# I2C-7-Segment-Backpack-dot56inch.net
KiCad netlist of a schematic drawn in EAGLE
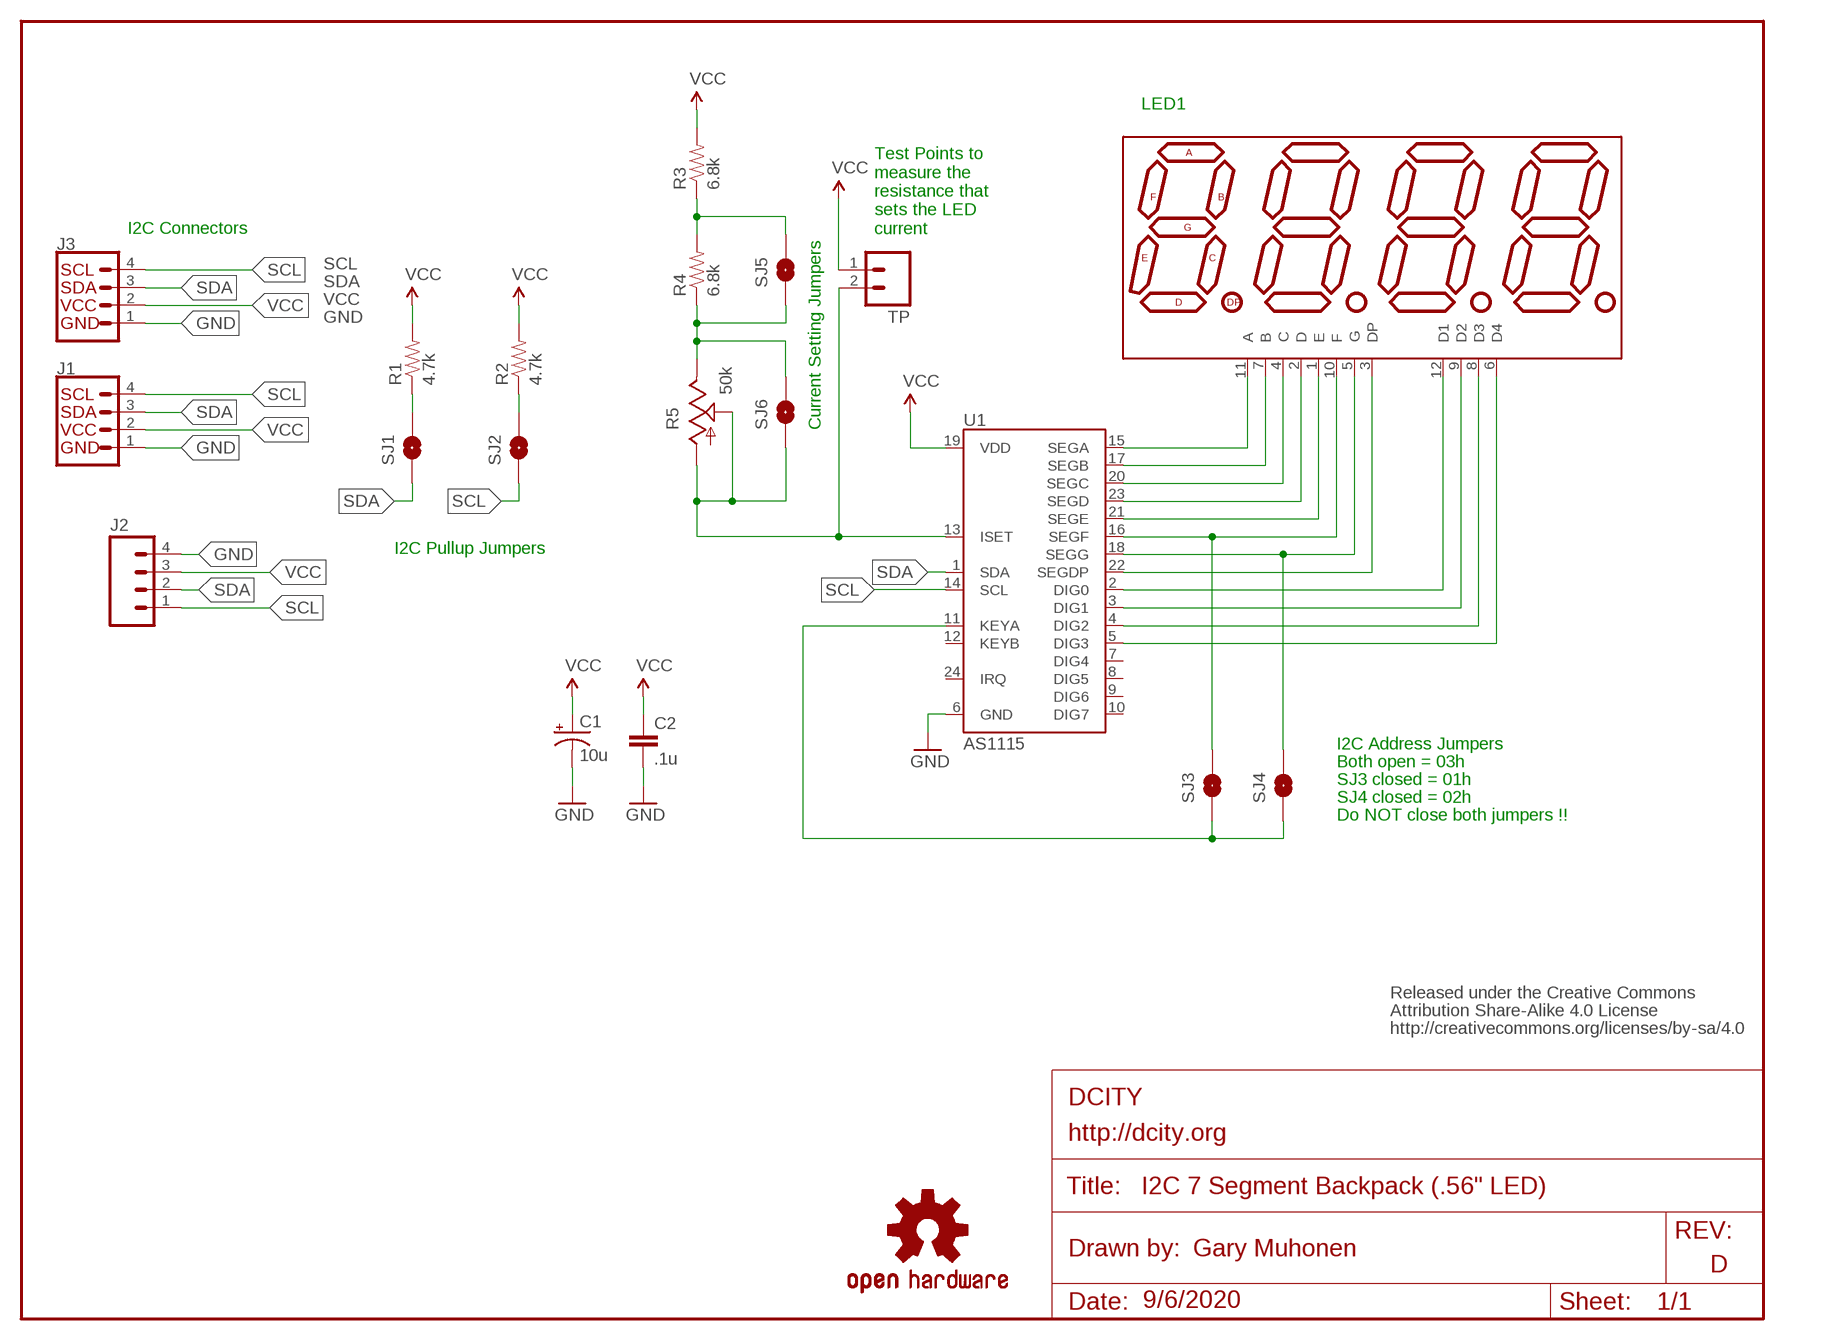
[diagram p0: schematic, sheet 1]

(export (version "E")
  (design (tool "Eeschema 10.0.6"))
  (components
    (comp (ref "C1")
      (value "10u")
      (footprint "eagle-import:0805-POL")
      (libsource (lib "eagle-import") (part "CAP_POL0805"))
    )
    (comp (ref "C2")
      (value ".1u")
      (footprint "eagle-import:0805-CAP")
      (libsource (lib "eagle-import") (part "CAP0805"))
    )
    (comp (ref "DISP1")
      (value "LED1")
      (footprint "eagle-import:7-SEGMENT-4DIGIT-PT6")
      (libsource (lib "eagle-import") (part "7-SEGMENT-4DIGIT-COUNTER-PT6"))
    )
    (comp (ref "J1")
      (value "QWIIC_RIGHT_ANGLE")
      (footprint "eagle-import:JST04_1MM_RA")
      (libsource (lib "eagle-import") (part "QWIIC_CONNECTORJS-1MM"))
    )
    (comp (ref "J2")
      (value "M04LOCK")
      (footprint "eagle-import:1X04_LOCK")
      (libsource (lib "eagle-import") (part "M04LOCK"))
    )
    (comp (ref "J3")
      (value "QWIIC_RIGHT_ANGLE")
      (footprint "eagle-import:JST04_1MM_RA")
      (libsource (lib "eagle-import") (part "QWIIC_CONNECTORJS-1MM"))
    )
    (comp (ref "LOGO1")
      (value "OSHW-LOGOS")
      (footprint "eagle-import:OSHW-LOGO-S")
      (libsource (lib "eagle-import") (part "OSHW-LOGOS"))
    )
    (comp (ref "R1")
      (value "4.7k")
      (footprint "eagle-import:0805-RES")
      (libsource (lib "eagle-import") (part "RESISTOR0805"))
    )
    (comp (ref "R2")
      (value "4.7k")
      (footprint "eagle-import:0805-RES")
      (libsource (lib "eagle-import") (part "RESISTOR0805"))
    )
    (comp (ref "R3")
      (value "6.8k")
      (footprint "eagle-import:0805-RES")
      (libsource (lib "eagle-import") (part "RESISTOR0805"))
    )
    (comp (ref "R4")
      (value "6.8k")
      (footprint "eagle-import:0805-RES")
      (libsource (lib "eagle-import") (part "RESISTOR0805"))
    )
    (comp (ref "R5")
      (value "50k")
      (footprint "eagle-import:POT-TC33X")
      (libsource (lib "eagle-import") (part "POT-TC33X"))
    )
    (comp (ref "SJ1")
      (value "SOLDERJUMPERNO")
      (footprint "eagle-import:SJ_2S-NO")
      (libsource (lib "eagle-import") (part "SOLDERJUMPERNO"))
    )
    (comp (ref "SJ2")
      (value "SOLDERJUMPERNO")
      (footprint "eagle-import:SJ_2S-NO")
      (libsource (lib "eagle-import") (part "SOLDERJUMPERNO"))
    )
    (comp (ref "SJ3")
      (value "SOLDERJUMPERNO")
      (footprint "eagle-import:SJ_2S-NO")
      (libsource (lib "eagle-import") (part "SOLDERJUMPERNO"))
    )
    (comp (ref "SJ4")
      (value "SOLDERJUMPERNO")
      (footprint "eagle-import:SJ_2S-NO")
      (libsource (lib "eagle-import") (part "SOLDERJUMPERNO"))
    )
    (comp (ref "SJ5")
      (value "SOLDERJUMPERNO")
      (footprint "eagle-import:SJ_2S-NO")
      (libsource (lib "eagle-import") (part "SOLDERJUMPERNO"))
    )
    (comp (ref "SJ6")
      (value "SOLDERJUMPERNO")
      (footprint "eagle-import:SJ_2S-NO")
      (libsource (lib "eagle-import") (part "SOLDERJUMPERNO"))
    )
    (comp (ref "TP")
      (value "M02PTH")
      (footprint "eagle-import:1X02")
      (libsource (lib "eagle-import") (part "M02PTH"))
    )
    (comp (ref "U$2")
      (value "CREATIVE_COMMONS")
      (footprint "eagle-import:CREATIVE_COMMONS")
      (libsource (lib "eagle-import") (part "CREATIVE_COMMONS"))
    )
    (comp (ref "U1")
      (value "AS1115")
      (footprint "eagle-import:TSSOP-24")
      (libsource (lib "eagle-import") (part "AS1115-LP"))
    )
  )
  (nets
    (net (code "1") (name "GND") (class "Default")
      (node (ref "C1") (pin "-") (pinfunction "-_-") (pintype "passive"))
      (node (ref "C2") (pin "2") (pinfunction "2_2") (pintype "passive"))
      (node (ref "J1") (pin "1") (pinfunction "1_1") (pintype "power_in"))
      (node (ref "J2") (pin "4") (pinfunction "4_4") (pintype "passive"))
      (node (ref "J3") (pin "1") (pinfunction "1_1") (pintype "power_in"))
      (node (ref "U1") (pin "6") (pinfunction "GND_6") (pintype "bidirectional"))
    )
    (net (code "2") (name "Net-(DISP1-A)") (class "Default")
      (node (ref "DISP1") (pin "11") (pinfunction "A_11") (pintype "bidirectional"))
      (node (ref "U1") (pin "15") (pinfunction "SEGA_15") (pintype "bidirectional"))
    )
    (net (code "3") (name "Net-(DISP1-B)") (class "Default")
      (node (ref "DISP1") (pin "7") (pinfunction "B_7") (pintype "bidirectional"))
      (node (ref "U1") (pin "17") (pinfunction "SEGB_17") (pintype "bidirectional"))
    )
    (net (code "4") (name "Net-(DISP1-C)") (class "Default")
      (node (ref "DISP1") (pin "4") (pinfunction "C_4") (pintype "bidirectional"))
      (node (ref "U1") (pin "20") (pinfunction "SEGC_20") (pintype "bidirectional"))
    )
    (net (code "5") (name "Net-(DISP1-D)") (class "Default")
      (node (ref "DISP1") (pin "2") (pinfunction "D_2") (pintype "bidirectional"))
      (node (ref "U1") (pin "23") (pinfunction "SEGD_23") (pintype "bidirectional"))
    )
    (net (code "6") (name "Net-(DISP1-D1)") (class "Default")
      (node (ref "DISP1") (pin "12") (pinfunction "D1_12") (pintype "bidirectional"))
      (node (ref "U1") (pin "2") (pinfunction "DIG0_2") (pintype "bidirectional"))
    )
    (net (code "7") (name "Net-(DISP1-D2)") (class "Default")
      (node (ref "DISP1") (pin "9") (pinfunction "D2_9") (pintype "bidirectional"))
      (node (ref "U1") (pin "3") (pinfunction "DIG1_3") (pintype "bidirectional"))
    )
    (net (code "8") (name "Net-(DISP1-D3)") (class "Default")
      (node (ref "DISP1") (pin "8") (pinfunction "D3_8") (pintype "bidirectional"))
      (node (ref "U1") (pin "4") (pinfunction "DIG2_4") (pintype "bidirectional"))
    )
    (net (code "9") (name "Net-(DISP1-D4)") (class "Default")
      (node (ref "DISP1") (pin "6") (pinfunction "D4_6") (pintype "bidirectional"))
      (node (ref "U1") (pin "5") (pinfunction "DIG3_5") (pintype "bidirectional"))
    )
    (net (code "10") (name "Net-(DISP1-DP)") (class "Default")
      (node (ref "DISP1") (pin "3") (pinfunction "DP_3") (pintype "bidirectional"))
      (node (ref "U1") (pin "22") (pinfunction "SEGDP_22") (pintype "bidirectional"))
    )
    (net (code "11") (name "Net-(DISP1-E)") (class "Default")
      (node (ref "DISP1") (pin "1") (pinfunction "E_1") (pintype "bidirectional"))
      (node (ref "U1") (pin "21") (pinfunction "SEGE_21") (pintype "bidirectional"))
    )
    (net (code "12") (name "Net-(DISP1-F)") (class "Default")
      (node (ref "DISP1") (pin "10") (pinfunction "F_10") (pintype "bidirectional"))
      (node (ref "SJ3") (pin "2") (pinfunction "2_2") (pintype "passive"))
      (node (ref "U1") (pin "16") (pinfunction "SEGF_16") (pintype "bidirectional"))
    )
    (net (code "13") (name "Net-(DISP1-G)") (class "Default")
      (node (ref "DISP1") (pin "5") (pinfunction "G_5") (pintype "bidirectional"))
      (node (ref "SJ4") (pin "2") (pinfunction "2_2") (pintype "passive"))
      (node (ref "U1") (pin "18") (pinfunction "SEGG_18") (pintype "bidirectional"))
    )
    (net (code "14") (name "Net-(R1-Pad1)") (class "Default")
      (node (ref "R1") (pin "1") (pinfunction "1_1") (pintype "passive"))
      (node (ref "SJ1") (pin "2") (pinfunction "2_2") (pintype "passive"))
    )
    (net (code "15") (name "Net-(R2-Pad1)") (class "Default")
      (node (ref "R2") (pin "1") (pinfunction "1_1") (pintype "passive"))
      (node (ref "SJ2") (pin "2") (pinfunction "2_2") (pintype "passive"))
    )
    (net (code "16") (name "Net-(R3-Pad1)") (class "Default")
      (node (ref "R3") (pin "1") (pinfunction "1_1") (pintype "passive"))
      (node (ref "R4") (pin "2") (pinfunction "2_2") (pintype "passive"))
      (node (ref "SJ5") (pin "2") (pinfunction "2_2") (pintype "passive"))
    )
    (net (code "17") (name "Net-(R5-A)") (class "Default")
      (node (ref "R5") (pin "1") (pinfunction "A_1") (pintype "passive"))
      (node (ref "R5") (pin "2") (pinfunction "S_2") (pintype "passive"))
      (node (ref "SJ6") (pin "1") (pinfunction "1_1") (pintype "passive"))
      (node (ref "TP") (pin "2") (pinfunction "2_2") (pintype "passive"))
      (node (ref "U1") (pin "13") (pinfunction "ISET_13") (pintype "bidirectional"))
    )
    (net (code "18") (name "Net-(R5-E)") (class "Default")
      (node (ref "R4") (pin "1") (pinfunction "1_1") (pintype "passive"))
      (node (ref "R5") (pin "3") (pinfunction "E_3") (pintype "passive"))
      (node (ref "SJ5") (pin "1") (pinfunction "1_1") (pintype "passive"))
      (node (ref "SJ6") (pin "2") (pinfunction "2_2") (pintype "passive"))
    )
    (net (code "19") (name "Net-(U1-KEYA)") (class "Default")
      (node (ref "SJ3") (pin "1") (pinfunction "1_1") (pintype "passive"))
      (node (ref "SJ4") (pin "1") (pinfunction "1_1") (pintype "passive"))
      (node (ref "U1") (pin "11") (pinfunction "KEYA_11") (pintype "bidirectional"))
    )
    (net (code "20") (name "SCL") (class "Default")
      (node (ref "J1") (pin "4") (pinfunction "4_4") (pintype "passive"))
      (node (ref "J2") (pin "1") (pinfunction "1_1") (pintype "passive"))
      (node (ref "J3") (pin "4") (pinfunction "4_4") (pintype "passive"))
      (node (ref "SJ2") (pin "1") (pinfunction "1_1") (pintype "passive"))
      (node (ref "U1") (pin "14") (pinfunction "SCL_14") (pintype "bidirectional"))
    )
    (net (code "21") (name "SDA") (class "Default")
      (node (ref "J1") (pin "3") (pinfunction "3_3") (pintype "passive"))
      (node (ref "J2") (pin "2") (pinfunction "2_2") (pintype "passive"))
      (node (ref "J3") (pin "3") (pinfunction "3_3") (pintype "passive"))
      (node (ref "SJ1") (pin "1") (pinfunction "1_1") (pintype "passive"))
      (node (ref "U1") (pin "1") (pinfunction "SDA_1") (pintype "bidirectional"))
    )
    (net (code "22") (name "VCC") (class "Default")
      (node (ref "C1") (pin "+") (pinfunction "+_+") (pintype "passive"))
      (node (ref "C2") (pin "1") (pinfunction "1_1") (pintype "passive"))
      (node (ref "J1") (pin "2") (pinfunction "2_2") (pintype "power_in"))
      (node (ref "J2") (pin "3") (pinfunction "3_3") (pintype "passive"))
      (node (ref "J3") (pin "2") (pinfunction "2_2") (pintype "power_in"))
      (node (ref "R1") (pin "2") (pinfunction "2_2") (pintype "passive"))
      (node (ref "R2") (pin "2") (pinfunction "2_2") (pintype "passive"))
      (node (ref "R3") (pin "2") (pinfunction "2_2") (pintype "passive"))
      (node (ref "TP") (pin "1") (pinfunction "1_1") (pintype "passive"))
      (node (ref "U1") (pin "19") (pinfunction "VDD_19") (pintype "bidirectional"))
    )
    (net (code "23") (name "unconnected-(U1-DIG4-Pad7)") (class "Default")
      (node (ref "U1") (pin "7") (pinfunction "DIG4_7") (pintype "bidirectional"))
    )
    (net (code "24") (name "unconnected-(U1-DIG5-Pad8)") (class "Default")
      (node (ref "U1") (pin "8") (pinfunction "DIG5_8") (pintype "bidirectional"))
    )
    (net (code "25") (name "unconnected-(U1-DIG6-Pad9)") (class "Default")
      (node (ref "U1") (pin "9") (pinfunction "DIG6_9") (pintype "bidirectional"))
    )
    (net (code "26") (name "unconnected-(U1-DIG7-Pad10)") (class "Default")
      (node (ref "U1") (pin "10") (pinfunction "DIG7_10") (pintype "bidirectional"))
    )
    (net (code "27") (name "unconnected-(U1-IRQ-Pad24)") (class "Default")
      (node (ref "U1") (pin "24") (pinfunction "IRQ_24") (pintype "bidirectional"))
    )
    (net (code "28") (name "unconnected-(U1-KEYB-Pad12)") (class "Default")
      (node (ref "U1") (pin "12") (pinfunction "KEYB_12") (pintype "bidirectional"))
    )
  )
)
